# MCU025B_Connectors.net
KiCad netlist of a schematic drawn in Altium Designer
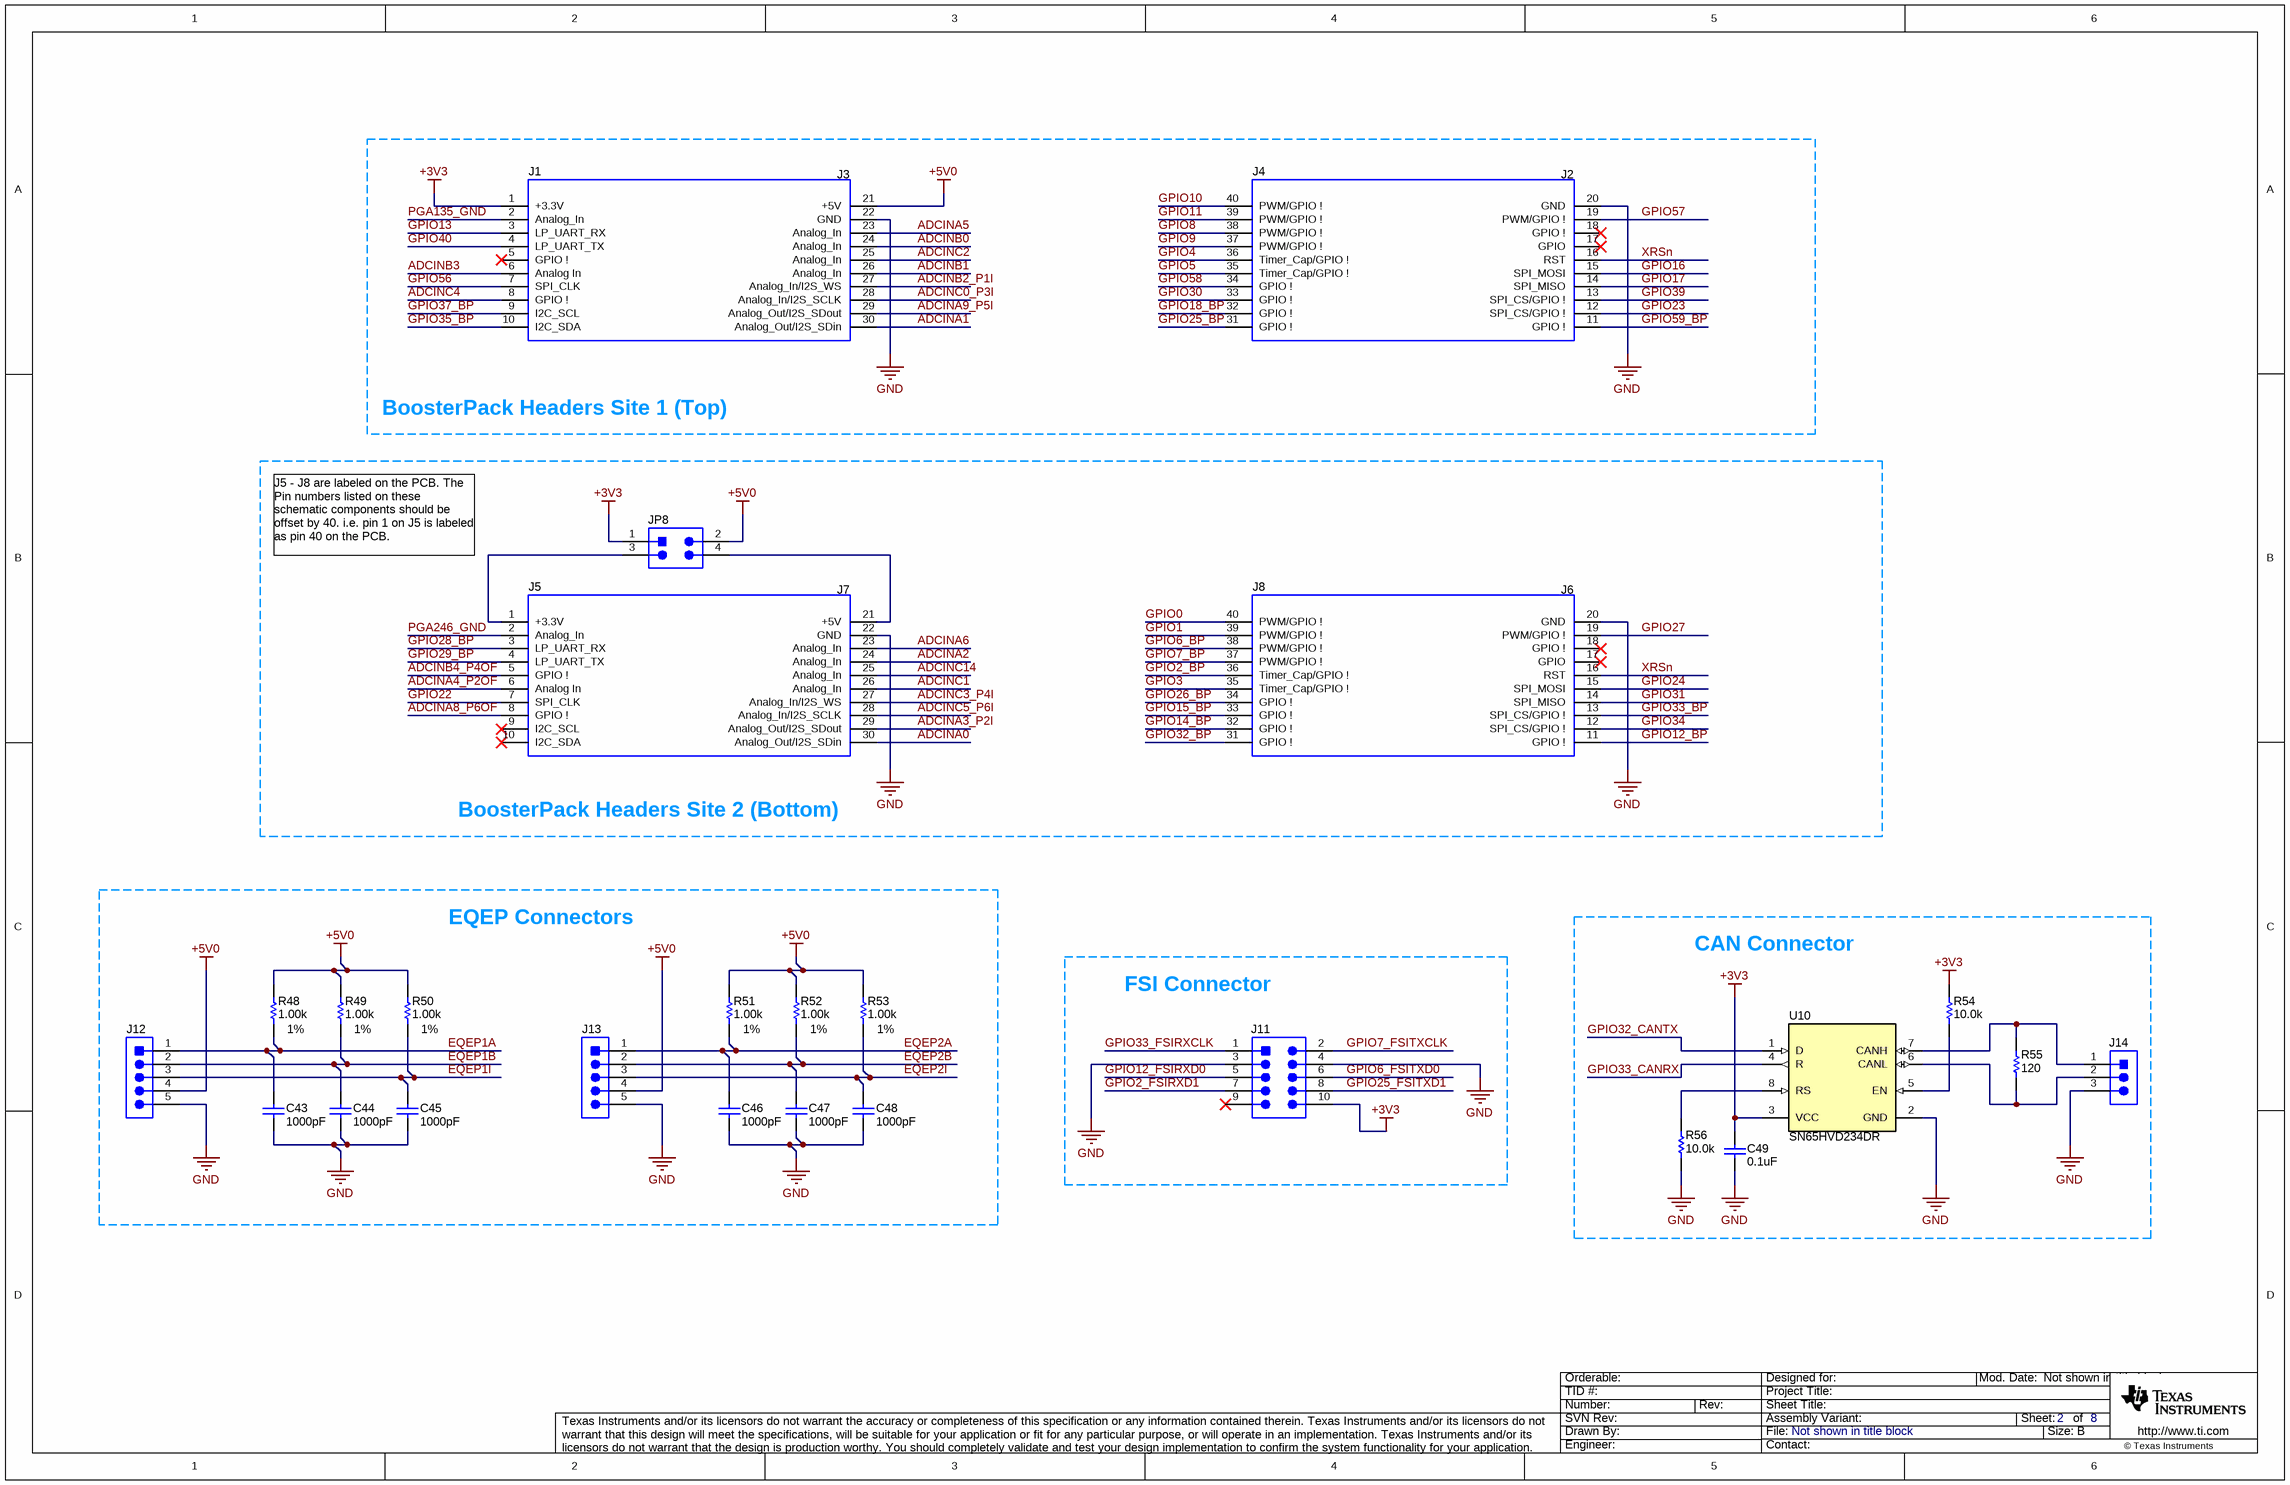
[diagram p0: MCU025B_Connectors.SchDoc]

(export (version "E")
  (design (tool "Eeschema 10.0.6"))
  (components
    (comp (ref "C43")
      (value "GRM155R71H102KA01D")
      (footprint "0402")
      (description "CAP, CERM, 1000 pF, 50 V, +/- 10%, X7R, 0402")
      (fields
        (field (name "VALUEDISPLAYED") "1000pF")
        (field (name "MANUFACTURER") "MuRata")
        (field (name "PUBLISHER") "Texas Instruments")
      )
      (libsource (lib "Altium Vault - TI") (part "Capacitor"))
    )
    (comp (ref "C44")
      (value "GRM155R71H102KA01D")
      (footprint "0402")
      (description "CAP, CERM, 1000 pF, 50 V, +/- 10%, X7R, 0402")
      (fields
        (field (name "VALUEDISPLAYED") "1000pF")
        (field (name "MANUFACTURER") "MuRata")
        (field (name "PUBLISHER") "Texas Instruments")
      )
      (libsource (lib "Altium Vault - TI") (part "Capacitor"))
    )
    (comp (ref "C45")
      (value "GRM155R71H102KA01D")
      (footprint "0402")
      (description "CAP, CERM, 1000 pF, 50 V, +/- 10%, X7R, 0402")
      (fields
        (field (name "VALUEDISPLAYED") "1000pF")
        (field (name "MANUFACTURER") "MuRata")
        (field (name "PUBLISHER") "Texas Instruments")
      )
      (libsource (lib "Altium Vault - TI") (part "Capacitor"))
    )
    (comp (ref "C46")
      (value "GRM155R71H102KA01D")
      (footprint "0402")
      (description "CAP, CERM, 1000 pF, 50 V, +/- 10%, X7R, 0402")
      (fields
        (field (name "VALUEDISPLAYED") "1000pF")
        (field (name "MANUFACTURER") "MuRata")
        (field (name "PUBLISHER") "Texas Instruments")
      )
      (libsource (lib "Altium Vault - TI") (part "Capacitor"))
    )
    (comp (ref "C47")
      (value "GRM155R71H102KA01D")
      (footprint "0402")
      (description "CAP, CERM, 1000 pF, 50 V, +/- 10%, X7R, 0402")
      (fields
        (field (name "VALUEDISPLAYED") "1000pF")
        (field (name "MANUFACTURER") "MuRata")
        (field (name "PUBLISHER") "Texas Instruments")
      )
      (libsource (lib "Altium Vault - TI") (part "Capacitor"))
    )
    (comp (ref "C48")
      (value "GRM155R71H102KA01D")
      (footprint "0402")
      (description "CAP, CERM, 1000 pF, 50 V, +/- 10%, X7R, 0402")
      (fields
        (field (name "VALUEDISPLAYED") "1000pF")
        (field (name "MANUFACTURER") "MuRata")
        (field (name "PUBLISHER") "Texas Instruments")
      )
      (libsource (lib "Altium Vault - TI") (part "Capacitor"))
    )
    (comp (ref "C49")
      (value "GRM155R71A104KA01D")
      (footprint "0402")
      (description "CAP, CERM, 0.1 uF, 10 V, +/- 10%, X7R, 0402")
      (fields
        (field (name "VALUEDISPLAYED") "0.1uF")
        (field (name "MANUFACTURER") "MuRata")
        (field (name "PUBLISHER") "Texas Instruments")
      )
      (libsource (lib "Altium Vault - TI") (part "Capacitor"))
    )
    (comp (ref "J1")
      (value "SSQ-110-03-T-D")
      (footprint "BoosterPack_40pin_J1J3")
      (description "Receptacle, 2.54mm, 10x2, Tin, TH")
      (fields (field (name "MANUFACTURER") "Samtec") (field (name "ALTERNATE PARTNUMBER") "CRD-081413-A-G"))
      (libsource (lib "Altium Vault - TI") (part "BoosterPack_40pin_J1J3"))
    )
    (comp (ref "J4")
      (value "SSQ-110-03-T-D")
      (footprint "BoosterPack_40pin_J2J4")
      (description "Receptacle, 2.54mm, 10x2, Tin, TH")
      (fields (field (name "MANUFACTURER") "Samtec") (field (name "ALTERNATE PARTNUMBER") "CRD-081413-A-G"))
      (libsource (lib "Altium Vault - TI") (part "BoosterPack_40pin_J2J4"))
    )
    (comp (ref "J5")
      (value "SSQ-110-03-T-D")
      (footprint "BoosterPack_40pin_J1J3")
      (description "Receptacle, 2.54mm, 10x2, Tin, TH")
      (fields (field (name "MANUFACTURER") "Samtec") (field (name "ALTERNATE PARTNUMBER") "CRD-081413-A-G"))
      (libsource (lib "Altium Vault - TI") (part "BoosterPack_40pin_J1J3"))
    )
    (comp (ref "J8")
      (value "SSQ-110-03-T-D")
      (footprint "BoosterPack_40pin_J2J4")
      (description "Receptacle, 2.54mm, 10x2, Tin, TH")
      (fields (field (name "MANUFACTURER") "Samtec") (field (name "ALTERNATE PARTNUMBER") "CRD-081413-A-G"))
      (libsource (lib "Altium Vault - TI") (part "BoosterPack_40pin_J2J4"))
    )
    (comp (ref "J11")
      (value "TSW-105-07-G-D")
      (footprint "TSW-105-07-G-D")
      (description "Header, 100mil, 5x2, Gold, TH")
      (fields (field (name "MANUFACTURER") "Samtec"))
      (libsource (lib "Altium Vault - TI") (part "Header_5x2"))
    )
    (comp (ref "J12")
      (value "TSW-105-07-G-S")
      (footprint "TSW-105-07-X-S")
      (description "Header, 100mil, 5x1, Gold, TH")
      (fields (field (name "MANUFACTURER") "Samtec") (field (name "PUBLISHER") "Texas Instruments"))
      (libsource (lib "Altium Vault - TI") (part "Header_5x1"))
    )
    (comp (ref "J13")
      (value "TSW-105-07-G-S")
      (footprint "TSW-105-07-X-S")
      (description "Header, 100mil, 5x1, Gold, TH")
      (fields (field (name "MANUFACTURER") "Samtec") (field (name "PUBLISHER") "Texas Instruments"))
      (libsource (lib "Altium Vault - TI") (part "Header_5x1"))
    )
    (comp (ref "J14")
      (value "61300311121")
      (footprint "WURTH_61300311121")
      (description "Header, 2.54 mm, 3x1, Gold, TH")
      (fields (field (name "MANUFACTURER") "Wurth Elektronik") (field (name "PUBLISHER") "Texas Instruments"))
      (libsource (lib "Altium Vault - TI") (part "CMP-0054796-1"))
    )
    (comp (ref "JP8")
      (value "TSW-102-07-G-D")
      (footprint "TSW-102-07-G-D")
      (description "Header, 100mil, 2x2, Gold, TH")
      (fields (field (name "MANUFACTURER") "Samtec") (field (name "PUBLISHER") "Texas Instruments"))
      (libsource (lib "Altium Vault - TI") (part "Header_2x2"))
    )
    (comp (ref "R48")
      (value "CRCW04021K00FKED")
      (footprint "0402")
      (description "RES, 1.00 k, 1%, 0.063 W, AEC-Q200 Grade 0, 0402")
      (fields
        (field (name "VALUEDISPLAYED") "1.00k")
        (field (name "MANUFACTURER") "Vishay-Dale")
        (field (name "VALUE1") "1%")
      )
      (libsource (lib "Altium Vault - TI") (part "Resistor"))
    )
    (comp (ref "R49")
      (value "CRCW04021K00FKED")
      (footprint "0402")
      (description "RES, 1.00 k, 1%, 0.063 W, AEC-Q200 Grade 0, 0402")
      (fields
        (field (name "VALUEDISPLAYED") "1.00k")
        (field (name "MANUFACTURER") "Vishay-Dale")
        (field (name "VALUE1") "1%")
      )
      (libsource (lib "Altium Vault - TI") (part "Resistor"))
    )
    (comp (ref "R50")
      (value "CRCW04021K00FKED")
      (footprint "0402")
      (description "RES, 1.00 k, 1%, 0.063 W, AEC-Q200 Grade 0, 0402")
      (fields
        (field (name "VALUEDISPLAYED") "1.00k")
        (field (name "MANUFACTURER") "Vishay-Dale")
        (field (name "VALUE1") "1%")
      )
      (libsource (lib "Altium Vault - TI") (part "Resistor"))
    )
    (comp (ref "R51")
      (value "CRCW04021K00FKED")
      (footprint "0402")
      (description "RES, 1.00 k, 1%, 0.063 W, AEC-Q200 Grade 0, 0402")
      (fields
        (field (name "VALUEDISPLAYED") "1.00k")
        (field (name "MANUFACTURER") "Vishay-Dale")
        (field (name "VALUE1") "1%")
      )
      (libsource (lib "Altium Vault - TI") (part "Resistor"))
    )
    (comp (ref "R52")
      (value "CRCW04021K00FKED")
      (footprint "0402")
      (description "RES, 1.00 k, 1%, 0.063 W, AEC-Q200 Grade 0, 0402")
      (fields
        (field (name "VALUEDISPLAYED") "1.00k")
        (field (name "MANUFACTURER") "Vishay-Dale")
        (field (name "VALUE1") "1%")
      )
      (libsource (lib "Altium Vault - TI") (part "Resistor"))
    )
    (comp (ref "R53")
      (value "CRCW04021K00FKED")
      (footprint "0402")
      (description "RES, 1.00 k, 1%, 0.063 W, AEC-Q200 Grade 0, 0402")
      (fields
        (field (name "VALUEDISPLAYED") "1.00k")
        (field (name "MANUFACTURER") "Vishay-Dale")
        (field (name "VALUE1") "1%")
      )
      (libsource (lib "Altium Vault - TI") (part "Resistor"))
    )
    (comp (ref "R54")
      (value "CRCW040210K0FKED")
      (footprint "0402")
      (description "RES, 10.0 k, 1%, 0.063 W, AEC-Q200 Grade 0, 0402")
      (fields (field (name "VALUEDISPLAYED") "10.0k") (field (name "MANUFACTURER") "Vishay-Dale"))
      (libsource (lib "Altium Vault - TI") (part "Resistor"))
    )
    (comp (ref "R55")
      (value "RC0603FR-07120RL")
      (footprint "0603")
      (description "RES, 120, 1%, 0.1 W, 0603")
      (fields
        (field (name "VALUEDISPLAYED") "120")
        (field (name "MANUFACTURER") "Yageo America")
        (field (name "PUBLISHER") "Texas Instruments")
      )
      (libsource (lib "Altium Vault - TI") (part "Resistor"))
    )
    (comp (ref "R56")
      (value "CRCW040210K0FKED")
      (footprint "0402")
      (description "RES, 10.0 k, 1%, 0.063 W, AEC-Q200 Grade 0, 0402")
      (fields (field (name "VALUEDISPLAYED") "10.0k") (field (name "MANUFACTURER") "Vishay-Dale"))
      (libsource (lib "Altium Vault - TI") (part "Resistor"))
    )
    (comp (ref "U10")
      (value "SN65HVD234DR")
      (footprint "D0008A_L")
      (fields (field (name "MANUFACTURER") "Texas Instruments"))
      (libsource (lib "Altium Vault - TI") (part "TI-SN65HVD234-SOIC_D-8"))
    )
  )
  (nets
    (net (code "1") (name "+3V3") (class "Default")
      (node (ref "C49") (pin "2") (pinfunction "2_2") (pintype "passive"))
      (node (ref "J1") (pin "1") (pinfunction "+3.3V_1") (pintype "power_in"))
      (node (ref "J11") (pin "10") (pinfunction "10_10") (pintype "passive"))
      (node (ref "JP8") (pin "1") (pinfunction "1_1") (pintype "passive"))
      (node (ref "R54") (pin "2") (pinfunction "2_2") (pintype "passive"))
      (node (ref "U10") (pin "3") (pinfunction "VCC_3") (pintype "power_in"))
    )
    (net (code "2") (name "+5V0") (class "Default")
      (node (ref "J1") (pin "21") (pinfunction "+5V_21") (pintype "power_in"))
      (node (ref "J12") (pin "4") (pinfunction "4_4") (pintype "passive"))
      (node (ref "J13") (pin "4") (pinfunction "4_4") (pintype "passive"))
      (node (ref "JP8") (pin "2") (pinfunction "2_2") (pintype "passive"))
      (node (ref "R48") (pin "2") (pinfunction "2_2") (pintype "passive"))
      (node (ref "R49") (pin "2") (pinfunction "2_2") (pintype "passive"))
      (node (ref "R50") (pin "2") (pinfunction "2_2") (pintype "passive"))
      (node (ref "R51") (pin "2") (pinfunction "2_2") (pintype "passive"))
      (node (ref "R52") (pin "2") (pinfunction "2_2") (pintype "passive"))
      (node (ref "R53") (pin "2") (pinfunction "2_2") (pintype "passive"))
    )
    (net (code "3") (name "/ADCINA0") (class "Default")
      (node (ref "J5") (pin "30") (pinfunction "Analog_Out/I2S_SDin_30") (pintype "passive"))
    )
    (net (code "4") (name "/ADCINA1") (class "Default")
      (node (ref "J1") (pin "30") (pinfunction "Analog_Out/I2S_SDin_30") (pintype "passive"))
    )
    (net (code "5") (name "/ADCINA2") (class "Default")
      (node (ref "J5") (pin "24") (pinfunction "Analog_In_24") (pintype "passive"))
    )
    (net (code "6") (name "/ADCINA3_P2I") (class "Default")
      (node (ref "J5") (pin "29") (pinfunction "Analog_Out/I2S_SDout_29") (pintype "passive"))
    )
    (net (code "7") (name "/ADCINA4_P2OF") (class "Default")
      (node (ref "J5") (pin "6") (pinfunction "Analog_In_6") (pintype "passive"))
    )
    (net (code "8") (name "/ADCINA5") (class "Default")
      (node (ref "J1") (pin "23") (pinfunction "Analog_In_23") (pintype "passive"))
    )
    (net (code "9") (name "/ADCINA6") (class "Default")
      (node (ref "J5") (pin "23") (pinfunction "Analog_In_23") (pintype "passive"))
    )
    (net (code "10") (name "/ADCINA8_P6OF") (class "Default")
      (node (ref "J5") (pin "8") (pinfunction "GPIO_!_8") (pintype "passive"))
    )
    (net (code "11") (name "/ADCINA9_P5I") (class "Default")
      (node (ref "J1") (pin "29") (pinfunction "Analog_Out/I2S_SDout_29") (pintype "passive"))
    )
    (net (code "12") (name "/ADCINB0") (class "Default")
      (node (ref "J1") (pin "24") (pinfunction "Analog_In_24") (pintype "passive"))
    )
    (net (code "13") (name "/ADCINB1") (class "Default")
      (node (ref "J1") (pin "26") (pinfunction "Analog_In_26") (pintype "passive"))
    )
    (net (code "14") (name "/ADCINB2_P1I") (class "Default")
      (node (ref "J1") (pin "27") (pinfunction "Analog_In/I2S_WS_27") (pintype "passive"))
    )
    (net (code "15") (name "/ADCINB3") (class "Default")
      (node (ref "J1") (pin "6") (pinfunction "Analog_In_6") (pintype "passive"))
    )
    (net (code "16") (name "/ADCINB4_P4OF") (class "Default")
      (node (ref "J5") (pin "5") (pinfunction "GPIO_!_5") (pintype "passive"))
    )
    (net (code "17") (name "/ADCINC0_P3I") (class "Default")
      (node (ref "J1") (pin "28") (pinfunction "Analog_In/I2S_SCLK_28") (pintype "passive"))
    )
    (net (code "18") (name "/ADCINC1") (class "Default")
      (node (ref "J5") (pin "26") (pinfunction "Analog_In_26") (pintype "passive"))
    )
    (net (code "19") (name "/ADCINC2") (class "Default")
      (node (ref "J1") (pin "25") (pinfunction "Analog_In_25") (pintype "passive"))
    )
    (net (code "20") (name "/ADCINC3_P4I") (class "Default")
      (node (ref "J5") (pin "27") (pinfunction "Analog_In/I2S_WS_27") (pintype "passive"))
    )
    (net (code "21") (name "/ADCINC4") (class "Default")
      (node (ref "J1") (pin "8") (pinfunction "GPIO_!_8") (pintype "passive"))
    )
    (net (code "22") (name "/ADCINC5_P6I") (class "Default")
      (node (ref "J5") (pin "28") (pinfunction "Analog_In/I2S_SCLK_28") (pintype "passive"))
    )
    (net (code "23") (name "/ADCINC14") (class "Default")
      (node (ref "J5") (pin "25") (pinfunction "Analog_In_25") (pintype "passive"))
    )
    (net (code "24") (name "/EQEP1A") (class "Default")
      (node (ref "C43") (pin "1") (pinfunction "1_1") (pintype "passive"))
      (node (ref "J12") (pin "1") (pinfunction "1_1") (pintype "passive"))
      (node (ref "R48") (pin "1") (pinfunction "1_1") (pintype "passive"))
    )
    (net (code "25") (name "/EQEP1B") (class "Default")
      (node (ref "C44") (pin "1") (pinfunction "1_1") (pintype "passive"))
      (node (ref "J12") (pin "2") (pinfunction "2_2") (pintype "passive"))
      (node (ref "R49") (pin "1") (pinfunction "1_1") (pintype "passive"))
    )
    (net (code "26") (name "/EQEP1I") (class "Default")
      (node (ref "C45") (pin "1") (pinfunction "1_1") (pintype "passive"))
      (node (ref "J12") (pin "3") (pinfunction "3_3") (pintype "passive"))
      (node (ref "R50") (pin "1") (pinfunction "1_1") (pintype "passive"))
    )
    (net (code "27") (name "/EQEP2A") (class "Default")
      (node (ref "C46") (pin "1") (pinfunction "1_1") (pintype "passive"))
      (node (ref "J13") (pin "1") (pinfunction "1_1") (pintype "passive"))
      (node (ref "R51") (pin "1") (pinfunction "1_1") (pintype "passive"))
    )
    (net (code "28") (name "/EQEP2B") (class "Default")
      (node (ref "C47") (pin "1") (pinfunction "1_1") (pintype "passive"))
      (node (ref "J13") (pin "2") (pinfunction "2_2") (pintype "passive"))
      (node (ref "R52") (pin "1") (pinfunction "1_1") (pintype "passive"))
    )
    (net (code "29") (name "/EQEP2I") (class "Default")
      (node (ref "C48") (pin "1") (pinfunction "1_1") (pintype "passive"))
      (node (ref "J13") (pin "3") (pinfunction "3_3") (pintype "passive"))
      (node (ref "R53") (pin "1") (pinfunction "1_1") (pintype "passive"))
    )
    (net (code "30") (name "/GPIO0") (class "Default")
      (node (ref "J8") (pin "40") (pinfunction "PWM/GPIO_!_40") (pintype "passive"))
    )
    (net (code "31") (name "/GPIO1") (class "Default")
      (node (ref "J8") (pin "39") (pinfunction "PWM/GPIO_!_39") (pintype "passive"))
    )
    (net (code "32") (name "/GPIO2_BP") (class "Default")
      (node (ref "J8") (pin "36") (pinfunction "Timer_Cap/GPIO_!_36") (pintype "passive"))
    )
    (net (code "33") (name "/GPIO2_FSIRXD1") (class "Default")
      (node (ref "J11") (pin "7") (pinfunction "7_7") (pintype "passive"))
    )
    (net (code "34") (name "/GPIO3") (class "Default")
      (node (ref "J8") (pin "35") (pinfunction "Timer_Cap/GPIO_!_35") (pintype "passive"))
    )
    (net (code "35") (name "/GPIO4") (class "Default")
      (node (ref "J4") (pin "36") (pinfunction "Timer_Cap/GPIO_!_36") (pintype "passive"))
    )
    (net (code "36") (name "/GPIO5") (class "Default")
      (node (ref "J4") (pin "35") (pinfunction "Timer_Cap/GPIO_!_35") (pintype "passive"))
    )
    (net (code "37") (name "/GPIO6_BP") (class "Default")
      (node (ref "J8") (pin "38") (pinfunction "PWM/GPIO_!_38") (pintype "passive"))
    )
    (net (code "38") (name "/GPIO6_FSITXD0") (class "Default")
      (node (ref "J11") (pin "6") (pinfunction "6_6") (pintype "passive"))
    )
    (net (code "39") (name "/GPIO7_BP") (class "Default")
      (node (ref "J8") (pin "37") (pinfunction "PWM/GPIO_!_37") (pintype "passive"))
    )
    (net (code "40") (name "/GPIO7_FSITXCLK") (class "Default")
      (node (ref "J11") (pin "2") (pinfunction "2_2") (pintype "passive"))
    )
    (net (code "41") (name "/GPIO8") (class "Default")
      (node (ref "J4") (pin "38") (pinfunction "PWM/GPIO_!_38") (pintype "passive"))
    )
    (net (code "42") (name "/GPIO9") (class "Default")
      (node (ref "J4") (pin "37") (pinfunction "PWM/GPIO_!_37") (pintype "passive"))
    )
    (net (code "43") (name "/GPIO10") (class "Default")
      (node (ref "J4") (pin "40") (pinfunction "PWM/GPIO_!_40") (pintype "passive"))
    )
    (net (code "44") (name "/GPIO11") (class "Default")
      (node (ref "J4") (pin "39") (pinfunction "PWM/GPIO_!_39") (pintype "passive"))
    )
    (net (code "45") (name "/GPIO12_BP") (class "Default")
      (node (ref "J8") (pin "11") (pinfunction "GPIO_!_11") (pintype "passive"))
    )
    (net (code "46") (name "/GPIO12_FSIRXD0") (class "Default")
      (node (ref "J11") (pin "5") (pinfunction "5_5") (pintype "passive"))
    )
    (net (code "47") (name "/GPIO13") (class "Default")
      (node (ref "J1") (pin "3") (pinfunction "LP_UART_RX_3") (pintype "passive"))
    )
    (net (code "48") (name "/GPIO14_BP") (class "Default")
      (node (ref "J8") (pin "32") (pinfunction "GPIO_!_32") (pintype "passive"))
    )
    (net (code "49") (name "/GPIO15_BP") (class "Default")
      (node (ref "J8") (pin "33") (pinfunction "GPIO_!_33") (pintype "passive"))
    )
    (net (code "50") (name "/GPIO16") (class "Default")
      (node (ref "J4") (pin "15") (pinfunction "SPI_MOSI_15") (pintype "passive"))
    )
    (net (code "51") (name "/GPIO17") (class "Default")
      (node (ref "J4") (pin "14") (pinfunction "SPI_MISO_14") (pintype "passive"))
    )
    (net (code "52") (name "/GPIO18_BP") (class "Default")
      (node (ref "J4") (pin "32") (pinfunction "GPIO_!_32") (pintype "passive"))
    )
    (net (code "53") (name "/GPIO22") (class "Default")
      (node (ref "J5") (pin "7") (pinfunction "SPI_CLK_7") (pintype "passive"))
    )
    (net (code "54") (name "/GPIO23") (class "Default")
      (node (ref "J4") (pin "12") (pinfunction "SPI_CS/GPIO_!_12") (pintype "passive"))
    )
    (net (code "55") (name "/GPIO24") (class "Default")
      (node (ref "J8") (pin "15") (pinfunction "SPI_MOSI_15") (pintype "passive"))
    )
    (net (code "56") (name "/GPIO25_BP") (class "Default")
      (node (ref "J4") (pin "31") (pinfunction "GPIO_!_31") (pintype "passive"))
    )
    (net (code "57") (name "/GPIO25_FSITXD1") (class "Default")
      (node (ref "J11") (pin "8") (pinfunction "8_8") (pintype "passive"))
    )
    (net (code "58") (name "/GPIO26_BP") (class "Default")
      (node (ref "J8") (pin "34") (pinfunction "GPIO_!_34") (pintype "passive"))
    )
    (net (code "59") (name "/GPIO27") (class "Default")
      (node (ref "J8") (pin "19") (pinfunction "PWM/GPIO_!_19") (pintype "passive"))
    )
    (net (code "60") (name "/GPIO28_BP") (class "Default")
      (node (ref "J5") (pin "3") (pinfunction "LP_UART_RX_3") (pintype "passive"))
    )
    (net (code "61") (name "/GPIO29_BP") (class "Default")
      (node (ref "J5") (pin "4") (pinfunction "LP_UART_TX_4") (pintype "passive"))
    )
    (net (code "62") (name "/GPIO30") (class "Default")
      (node (ref "J4") (pin "33") (pinfunction "GPIO_!_33") (pintype "passive"))
    )
    (net (code "63") (name "/GPIO31") (class "Default")
      (node (ref "J8") (pin "14") (pinfunction "SPI_MISO_14") (pintype "passive"))
    )
    (net (code "64") (name "/GPIO32_BP") (class "Default")
      (node (ref "J8") (pin "31") (pinfunction "GPIO_!_31") (pintype "passive"))
    )
    (net (code "65") (name "/GPIO32_CANTX") (class "Default")
      (node (ref "U10") (pin "1") (pinfunction "D_1") (pintype "input"))
    )
    (net (code "66") (name "/GPIO33_BP") (class "Default")
      (node (ref "J8") (pin "13") (pinfunction "SPI_CS/GPIO_!_13") (pintype "passive"))
    )
    (net (code "67") (name "/GPIO33_CANRX") (class "Default")
      (node (ref "U10") (pin "4") (pinfunction "R_4") (pintype "output"))
    )
    (net (code "68") (name "/GPIO33_FSIRXCLK") (class "Default")
      (node (ref "J11") (pin "1") (pinfunction "1_1") (pintype "passive"))
    )
    (net (code "69") (name "/GPIO34") (class "Default")
      (node (ref "J8") (pin "12") (pinfunction "SPI_CS/GPIO_!_12") (pintype "passive"))
    )
    (net (code "70") (name "/GPIO35_BP") (class "Default")
      (node (ref "J1") (pin "10") (pinfunction "I2C_SDA_10") (pintype "passive"))
    )
    (net (code "71") (name "/GPIO37_BP") (class "Default")
      (node (ref "J1") (pin "9") (pinfunction "I2C_SCL_9") (pintype "passive"))
    )
    (net (code "72") (name "/GPIO39") (class "Default")
      (node (ref "J4") (pin "13") (pinfunction "SPI_CS/GPIO_!_13") (pintype "passive"))
    )
    (net (code "73") (name "/GPIO40") (class "Default")
      (node (ref "J1") (pin "4") (pinfunction "LP_UART_TX_4") (pintype "passive"))
    )
    (net (code "74") (name "/GPIO56") (class "Default")
      (node (ref "J1") (pin "7") (pinfunction "SPI_CLK_7") (pintype "passive"))
    )
    (net (code "75") (name "/GPIO57") (class "Default")
      (node (ref "J4") (pin "19") (pinfunction "PWM/GPIO_!_19") (pintype "passive"))
    )
    (net (code "76") (name "/GPIO58") (class "Default")
      (node (ref "J4") (pin "34") (pinfunction "GPIO_!_34") (pintype "passive"))
    )
    (net (code "77") (name "/GPIO59_BP") (class "Default")
      (node (ref "J4") (pin "11") (pinfunction "GPIO_!_11") (pintype "passive"))
    )
    (net (code "78") (name "/PGA135_GND") (class "Default")
      (node (ref "J1") (pin "2") (pinfunction "Analog_In_2") (pintype "passive"))
    )
    (net (code "79") (name "/PGA246_GND") (class "Default")
      (node (ref "J5") (pin "2") (pinfunction "Analog_In_2") (pintype "passive"))
    )
    (net (code "80") (name "/XRSn") (class "Default")
      (node (ref "J4") (pin "16") (pinfunction "RST_16") (pintype "passive"))
      (node (ref "J8") (pin "16") (pinfunction "RST_16") (pintype "passive"))
    )
    (net (code "81") (name "GND") (class "Default")
      (node (ref "C43") (pin "2") (pinfunction "2_2") (pintype "passive"))
      (node (ref "C44") (pin "2") (pinfunction "2_2") (pintype "passive"))
      (node (ref "C45") (pin "2") (pinfunction "2_2") (pintype "passive"))
      (node (ref "C46") (pin "2") (pinfunction "2_2") (pintype "passive"))
      (node (ref "C47") (pin "2") (pinfunction "2_2") (pintype "passive"))
      (node (ref "C48") (pin "2") (pinfunction "2_2") (pintype "passive"))
      (node (ref "C49") (pin "1") (pinfunction "1_1") (pintype "passive"))
      (node (ref "J1") (pin "22") (pinfunction "GND_22") (pintype "power_in"))
      (node (ref "J11") (pin "3") (pinfunction "3_3") (pintype "passive"))
      (node (ref "J11") (pin "4") (pinfunction "4_4") (pintype "passive"))
      (node (ref "J12") (pin "5") (pinfunction "5_5") (pintype "passive"))
      (node (ref "J13") (pin "5") (pinfunction "5_5") (pintype "passive"))
      (node (ref "J14") (pin "3") (pinfunction "3_3") (pintype "passive"))
      (node (ref "J4") (pin "20") (pinfunction "GND_20") (pintype "power_in"))
      (node (ref "J5") (pin "22") (pinfunction "GND_22") (pintype "power_in"))
      (node (ref "J8") (pin "20") (pinfunction "GND_20") (pintype "power_in"))
      (node (ref "R56") (pin "1") (pinfunction "1_1") (pintype "passive"))
      (node (ref "U10") (pin "2") (pinfunction "GND_2") (pintype "power_in"))
    )
    (net (code "82") (name "Net-(J5-+3.3V)") (class "Default")
      (node (ref "J5") (pin "1") (pinfunction "+3.3V_1") (pintype "power_in"))
      (node (ref "JP8") (pin "3") (pinfunction "3_3") (pintype "passive"))
    )
    (net (code "83") (name "Net-(J5-+5V)") (class "Default")
      (node (ref "J5") (pin "21") (pinfunction "+5V_21") (pintype "power_in"))
      (node (ref "JP8") (pin "4") (pinfunction "4_4") (pintype "passive"))
    )
    (net (code "84") (name "Net-(U10-CANH)") (class "Default")
      (node (ref "J14") (pin "1") (pinfunction "1_1") (pintype "passive"))
      (node (ref "R55") (pin "2") (pinfunction "2_2") (pintype "passive"))
      (node (ref "U10") (pin "7") (pinfunction "CANH_7") (pintype "bidirectional"))
    )
    (net (code "85") (name "Net-(U10-CANL)") (class "Default")
      (node (ref "J14") (pin "2") (pinfunction "2_2") (pintype "passive"))
      (node (ref "R55") (pin "1") (pinfunction "1_1") (pintype "passive"))
      (node (ref "U10") (pin "6") (pinfunction "CANL_6") (pintype "bidirectional"))
    )
    (net (code "86") (name "Net-(U10-EN)") (class "Default")
      (node (ref "R54") (pin "1") (pinfunction "1_1") (pintype "passive"))
      (node (ref "U10") (pin "5") (pinfunction "EN_5") (pintype "input"))
    )
    (net (code "87") (name "Net-(U10-RS)") (class "Default")
      (node (ref "R56") (pin "2") (pinfunction "2_2") (pintype "passive"))
      (node (ref "U10") (pin "8") (pinfunction "RS_8") (pintype "input"))
    )
    (net (code "88") (name "unconnected-(J1-GPIO_!-Pad5)") (class "Default")
      (node (ref "J1") (pin "5") (pinfunction "GPIO_!_5") (pintype "passive+no_connect"))
    )
    (net (code "89") (name "unconnected-(J4-GPIO-Pad17)") (class "Default")
      (node (ref "J4") (pin "17") (pinfunction "GPIO_17") (pintype "passive+no_connect"))
    )
    (net (code "90") (name "unconnected-(J4-GPIO_!-Pad18)") (class "Default")
      (node (ref "J4") (pin "18") (pinfunction "GPIO_!_18") (pintype "passive+no_connect"))
    )
    (net (code "91") (name "unconnected-(J5-I2C_SCL-Pad9)") (class "Default")
      (node (ref "J5") (pin "9") (pinfunction "I2C_SCL_9") (pintype "passive+no_connect"))
    )
    (net (code "92") (name "unconnected-(J5-I2C_SDA-Pad10)") (class "Default")
      (node (ref "J5") (pin "10") (pinfunction "I2C_SDA_10") (pintype "passive+no_connect"))
    )
    (net (code "93") (name "unconnected-(J8-GPIO-Pad17)") (class "Default")
      (node (ref "J8") (pin "17") (pinfunction "GPIO_17") (pintype "passive+no_connect"))
    )
    (net (code "94") (name "unconnected-(J8-GPIO_!-Pad18)") (class "Default")
      (node (ref "J8") (pin "18") (pinfunction "GPIO_!_18") (pintype "passive+no_connect"))
    )
    (net (code "95") (name "unconnected-(J11-Pad9)") (class "Default")
      (node (ref "J11") (pin "9") (pinfunction "9_9") (pintype "passive+no_connect"))
    )
  )
)
